# band_psd_v1_1_shield.net
KiCad netlist of a schematic drawn in EAGLE
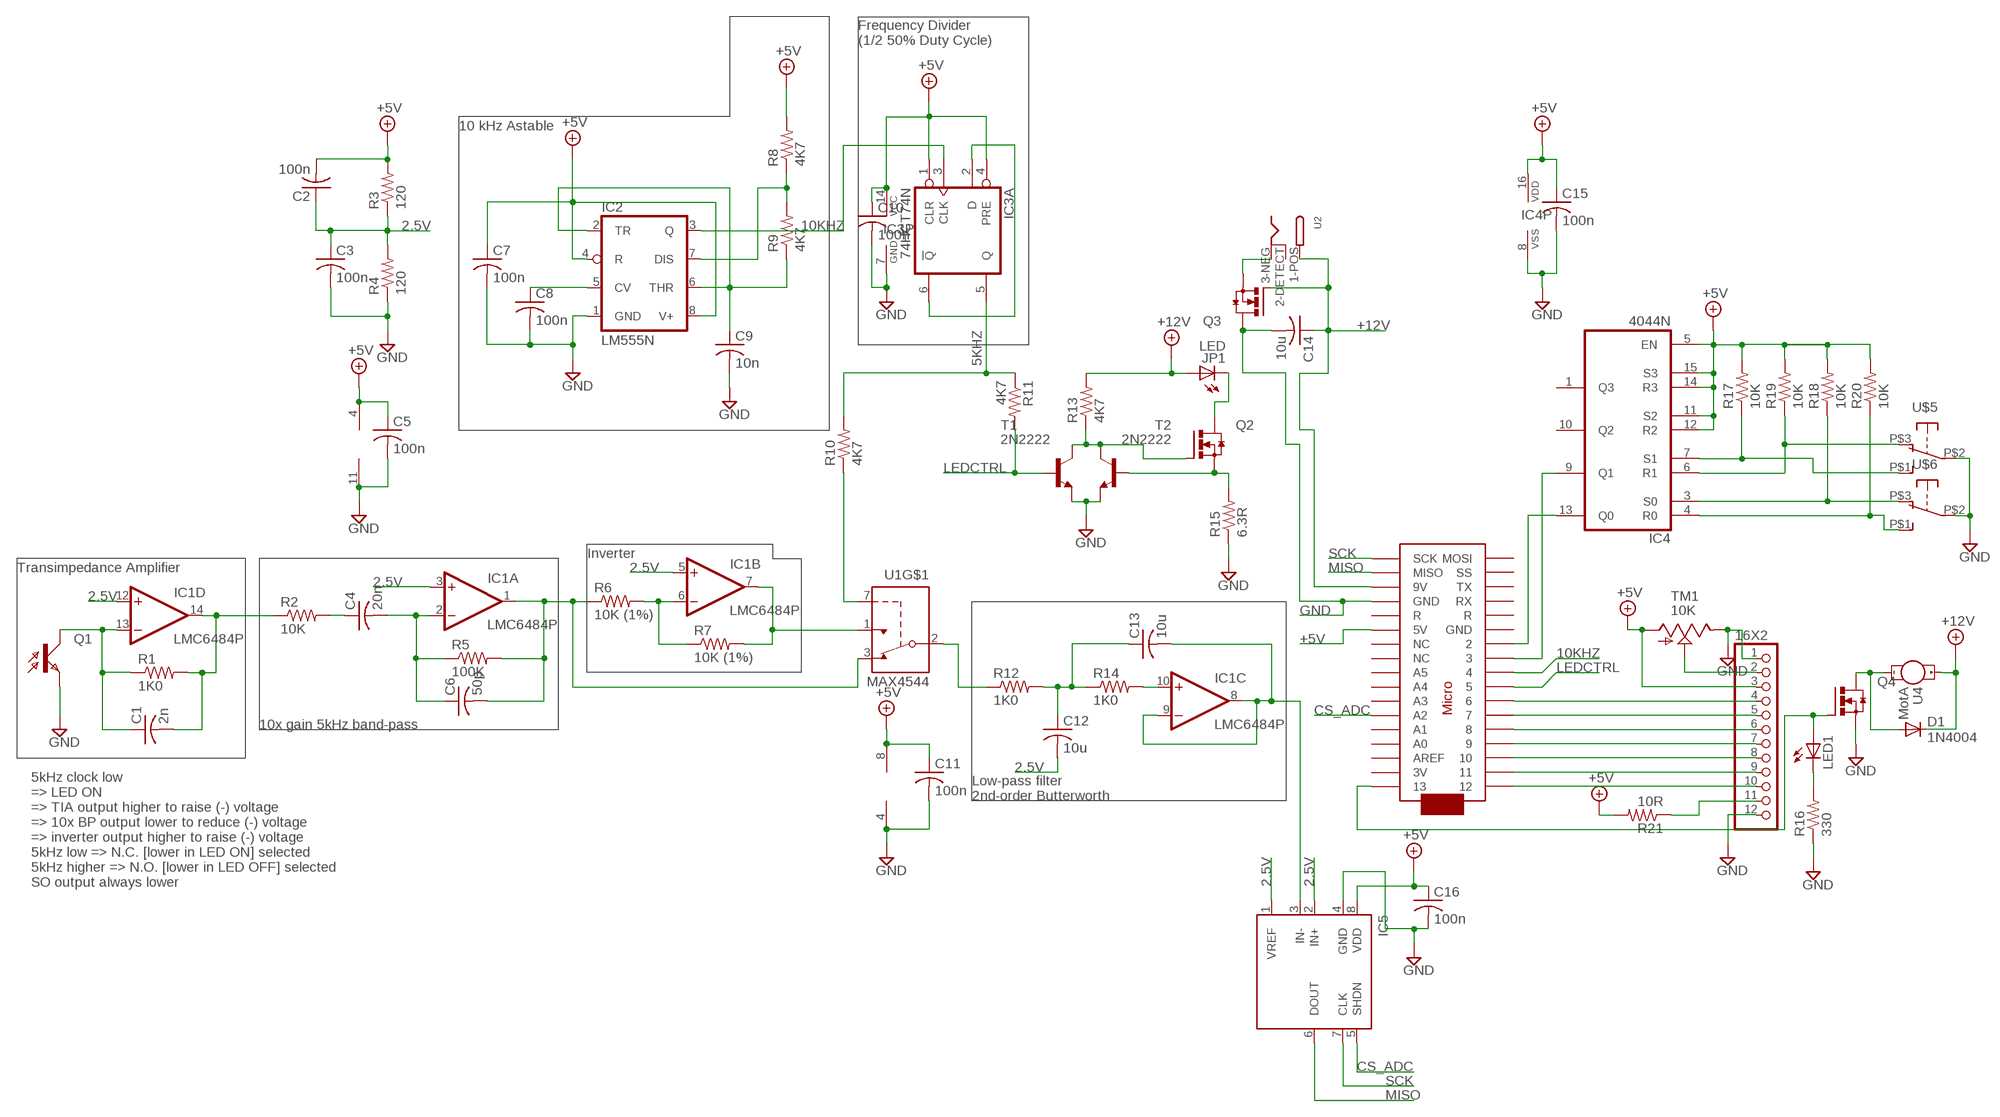
[diagram p0: schematic, sheet 1]

(export (version "E")
  (design (tool "Eeschema 10.0.6"))
  (components
    (comp (ref "16X2")
      (value "PINHD-1X12-CB")
      (footprint "eagle-import:1X12-CB")
      (libsource (lib "eagle-import") (part "PINHD-1X12-CB"))
    )
    (comp (ref "C1")
      (value "2n")
      (footprint "eagle-import:C025-025X050")
      (libsource (lib "eagle-import") (part "C-US025-025X050"))
    )
    (comp (ref "C2")
      (value "100n")
      (footprint "eagle-import:C025-025X050")
      (libsource (lib "eagle-import") (part "C-US025-025X050"))
    )
    (comp (ref "C3")
      (value "100n")
      (footprint "eagle-import:C025-025X050")
      (libsource (lib "eagle-import") (part "C-US025-025X050"))
    )
    (comp (ref "C4")
      (value "20n")
      (footprint "eagle-import:C025-025X050")
      (libsource (lib "eagle-import") (part "C-US025-025X050"))
    )
    (comp (ref "C5")
      (value "100n")
      (footprint "eagle-import:C025-025X050")
      (libsource (lib "eagle-import") (part "C-US025-025X050"))
    )
    (comp (ref "C6")
      (value "50p")
      (footprint "eagle-import:C025-025X050")
      (libsource (lib "eagle-import") (part "C-US025-025X050"))
    )
    (comp (ref "C7")
      (value "100n")
      (footprint "eagle-import:C025-025X050")
      (libsource (lib "eagle-import") (part "C-US025-025X050"))
    )
    (comp (ref "C8")
      (value "100n")
      (footprint "eagle-import:C025-025X050")
      (libsource (lib "eagle-import") (part "C-US025-025X050"))
    )
    (comp (ref "C9")
      (value "10n")
      (footprint "eagle-import:C025-025X050")
      (libsource (lib "eagle-import") (part "C-US025-025X050"))
    )
    (comp (ref "C10")
      (value "100n")
      (footprint "eagle-import:C025-025X050")
      (libsource (lib "eagle-import") (part "C-US025-025X050"))
    )
    (comp (ref "C11")
      (value "100n")
      (footprint "eagle-import:C025-025X050")
      (libsource (lib "eagle-import") (part "C-US025-025X050"))
    )
    (comp (ref "C12")
      (value "10u")
      (footprint "eagle-import:C050-025X075")
      (libsource (lib "eagle-import") (part "C-US050-025X075"))
    )
    (comp (ref "C13")
      (value "10u")
      (footprint "eagle-import:C050-025X075")
      (libsource (lib "eagle-import") (part "C-US050-025X075"))
    )
    (comp (ref "C14")
      (value "10u")
      (footprint "eagle-import:C050-050X075")
      (libsource (lib "eagle-import") (part "C-US050-050X075"))
    )
    (comp (ref "C15")
      (value "100n")
      (footprint "eagle-import:C025-025X050")
      (libsource (lib "eagle-import") (part "C-US025-025X050"))
    )
    (comp (ref "C16")
      (value "100n")
      (footprint "eagle-import:C025-025X050")
      (libsource (lib "eagle-import") (part "C-US025-025X050"))
    )
    (comp (ref "D1")
      (value "1N4004")
      (footprint "eagle-import:DO41-10")
      (libsource (lib "eagle-import") (part "1N4004"))
    )
    (comp (ref "IC1")
      (value "LMC6484P")
      (footprint "eagle-import:DIL14")
      (libsource (lib "eagle-import") (part "LMC6484P"))
    )
    (comp (ref "IC2")
      (value "LM555N")
      (footprint "eagle-import:DIL08")
      (libsource (lib "eagle-import") (part "555NLM"))
    )
    (comp (ref "IC3")
      (value "74HCT74N")
      (footprint "eagle-import:DIL14")
      (libsource (lib "eagle-import") (part "7474NHCT"))
    )
    (comp (ref "IC4")
      (value "4044N")
      (footprint "eagle-import:DIL16")
      (libsource (lib "eagle-import") (part "4044N"))
    )
    (comp (ref "IC5")
      (value "MCP3301")
      (footprint "eagle-import:DIL08")
      (libsource (lib "eagle-import") (part "MCP3301"))
    )
    (comp (ref "JP1")
      (value "LED")
      (footprint "eagle-import:1X02_SCREW")
      (libsource (lib "eagle-import") (part "LED_CXN"))
    )
    (comp (ref "LED1")
      (value "LED3MM")
      (footprint "eagle-import:LED3MM")
      (libsource (lib "eagle-import") (part "LED3MM"))
    )
    (comp (ref "Q1")
      (value "LTR-4206PTRANS")
      (footprint "eagle-import:PTRANS")
      (libsource (lib "eagle-import") (part "LTR-4206PTRANS"))
    )
    (comp (ref "Q2")
      (value "IRLB8721")
      (footprint "eagle-import:TO220BV")
      (libsource (lib "eagle-import") (part "IRLB8721"))
    )
    (comp (ref "Q3")
      (value "IRLB8721")
      (footprint "eagle-import:TO220BV")
      (libsource (lib "eagle-import") (part "IRLB8721"))
    )
    (comp (ref "Q4")
      (value "IRLB8721")
      (footprint "eagle-import:TO220BV")
      (libsource (lib "eagle-import") (part "IRLB8721"))
    )
    (comp (ref "R1")
      (value "1K0")
      (footprint "eagle-import:0204V")
      (libsource (lib "eagle-import") (part "R-US_0204/2V"))
    )
    (comp (ref "R2")
      (value "10K")
      (footprint "eagle-import:0204V")
      (libsource (lib "eagle-import") (part "R-US_0204/2V"))
    )
    (comp (ref "R3")
      (value "120")
      (footprint "eagle-import:0204V")
      (libsource (lib "eagle-import") (part "R-US_0204/2V"))
    )
    (comp (ref "R4")
      (value "120")
      (footprint "eagle-import:0204V")
      (libsource (lib "eagle-import") (part "R-US_0204/2V"))
    )
    (comp (ref "R5")
      (value "100K")
      (footprint "eagle-import:0204V")
      (libsource (lib "eagle-import") (part "R-US_0204/2V"))
    )
    (comp (ref "R6")
      (value "10K (1%)")
      (footprint "eagle-import:0204V")
      (libsource (lib "eagle-import") (part "R-US_0204/2V"))
    )
    (comp (ref "R7")
      (value "10K (1%)")
      (footprint "eagle-import:0204V")
      (libsource (lib "eagle-import") (part "R-US_0204/2V"))
    )
    (comp (ref "R8")
      (value "4K7")
      (footprint "eagle-import:0204V")
      (libsource (lib "eagle-import") (part "R-US_0204/2V"))
    )
    (comp (ref "R9")
      (value "4K7")
      (footprint "eagle-import:0204V")
      (libsource (lib "eagle-import") (part "R-US_0204/2V"))
    )
    (comp (ref "R10")
      (value "4K7")
      (footprint "eagle-import:0204V")
      (libsource (lib "eagle-import") (part "R-US_0204/2V"))
    )
    (comp (ref "R11")
      (value "4K7")
      (footprint "eagle-import:0204V")
      (libsource (lib "eagle-import") (part "R-US_0204/2V"))
    )
    (comp (ref "R12")
      (value "1K0")
      (footprint "eagle-import:0204V")
      (libsource (lib "eagle-import") (part "R-US_0204/2V"))
    )
    (comp (ref "R13")
      (value "4K7")
      (footprint "eagle-import:0204V")
      (libsource (lib "eagle-import") (part "R-US_0204/2V"))
    )
    (comp (ref "R14")
      (value "1K0")
      (footprint "eagle-import:0204V")
      (libsource (lib "eagle-import") (part "R-US_0204/2V"))
    )
    (comp (ref "R15")
      (value "6.3R")
      (footprint "eagle-import:0204V")
      (libsource (lib "eagle-import") (part "R-US_0204/2V"))
    )
    (comp (ref "R16")
      (value "330")
      (footprint "eagle-import:0204V")
      (libsource (lib "eagle-import") (part "R-US_0204/2V"))
    )
    (comp (ref "R17")
      (value "10K")
      (footprint "eagle-import:0204V")
      (libsource (lib "eagle-import") (part "R-US_0204/2V"))
    )
    (comp (ref "R18")
      (value "10K")
      (footprint "eagle-import:0204V")
      (libsource (lib "eagle-import") (part "R-US_0204/2V"))
    )
    (comp (ref "R19")
      (value "10K")
      (footprint "eagle-import:0204V")
      (libsource (lib "eagle-import") (part "R-US_0204/2V"))
    )
    (comp (ref "R20")
      (value "10K")
      (footprint "eagle-import:0204V")
      (libsource (lib "eagle-import") (part "R-US_0204/2V"))
    )
    (comp (ref "R21")
      (value "10R")
      (footprint "eagle-import:0204V")
      (libsource (lib "eagle-import") (part "R-US_0204/2V"))
    )
    (comp (ref "T1")
      (value "2N2222")
      (footprint "eagle-import:TO92-EBC-OVAL")
      (libsource (lib "eagle-import") (part "2N2222"))
    )
    (comp (ref "T2")
      (value "2N2222")
      (footprint "eagle-import:TO92-EBC-OVAL")
      (libsource (lib "eagle-import") (part "2N2222"))
    )
    (comp (ref "TM1")
      (value "10K")
      (footprint "eagle-import:B25P")
      (libsource (lib "eagle-import") (part "TRIM_US-B25P"))
    )
    (comp (ref "U$5")
      (value "APE1F-5M-10-Z")
      (footprint "eagle-import:APE1F-5M-10Z")
      (libsource (lib "eagle-import") (part "APE1F-5M-10-Z"))
    )
    (comp (ref "U$6")
      (value "APE1F-5M-10-Z")
      (footprint "eagle-import:APE1F-5M-10Z")
      (libsource (lib "eagle-import") (part "APE1F-5M-10-Z"))
    )
    (comp (ref "U1")
      (value "MAX4544")
      (footprint "eagle-import:DIL08")
      (libsource (lib "eagle-import") (part "MAX4544"))
    )
    (comp (ref "U2")
      (value "DC-IN-PANEL")
      (footprint "eagle-import:3WIRES")
      (libsource (lib "eagle-import") (part "DC-IN-PANEL"))
    )
    (comp (ref "U3")
      (value "ARDUINOMICRO")
      (footprint "eagle-import:ARDUINOMICRO")
      (libsource (lib "eagle-import") (part "ARDUINOMICRO"))
    )
    (comp (ref "U4")
      (value "MotA")
      (footprint "eagle-import:1X02_SCREW")
      (libsource (lib "eagle-import") (part "1X02_MOTOR"))
    )
  )
  (nets
    (net (code "1") (name "+5V") (class "Default")
      (node (ref "16X2") (pin "3") (pinfunction "3_3") (pintype "passive"))
      (node (ref "C10") (pin "1") (pinfunction "1_1") (pintype "passive"))
      (node (ref "C11") (pin "1") (pinfunction "1_1") (pintype "passive"))
      (node (ref "C15") (pin "1") (pinfunction "1_1") (pintype "passive"))
      (node (ref "C16") (pin "1") (pinfunction "1_1") (pintype "passive"))
      (node (ref "C2") (pin "2") (pinfunction "2_2") (pintype "passive"))
      (node (ref "C5") (pin "1") (pinfunction "1_1") (pintype "passive"))
      (node (ref "C7") (pin "1") (pinfunction "1_1") (pintype "passive"))
      (node (ref "IC1") (pin "4") (pinfunction "V+_4") (pintype "power_in"))
      (node (ref "IC2") (pin "4") (pinfunction "R_4") (pintype "input"))
      (node (ref "IC2") (pin "8") (pinfunction "V+_8") (pintype "power_in"))
      (node (ref "IC3") (pin "1") (pinfunction "CLR_1") (pintype "input"))
      (node (ref "IC3") (pin "14") (pinfunction "VCC_14") (pintype "power_in"))
      (node (ref "IC3") (pin "4") (pinfunction "PRE_4") (pintype "input"))
      (node (ref "IC4") (pin "11") (pinfunction "S2_11") (pintype "input"))
      (node (ref "IC4") (pin "12") (pinfunction "R2_12") (pintype "input"))
      (node (ref "IC4") (pin "14") (pinfunction "R3_14") (pintype "input"))
      (node (ref "IC4") (pin "15") (pinfunction "S3_15") (pintype "input"))
      (node (ref "IC4") (pin "16") (pinfunction "VDD_16") (pintype "power_in"))
      (node (ref "IC4") (pin "5") (pinfunction "EN_5") (pintype "input"))
      (node (ref "IC5") (pin "8") (pinfunction "VDD_8") (pintype "power_in"))
      (node (ref "R17") (pin "2") (pinfunction "2_2") (pintype "passive"))
      (node (ref "R18") (pin "2") (pinfunction "2_2") (pintype "passive"))
      (node (ref "R19") (pin "2") (pinfunction "2_2") (pintype "passive"))
      (node (ref "R20") (pin "2") (pinfunction "2_2") (pintype "passive"))
      (node (ref "R21") (pin "2") (pinfunction "2_2") (pintype "passive"))
      (node (ref "R3") (pin "2") (pinfunction "2_2") (pintype "passive"))
      (node (ref "R8") (pin "2") (pinfunction "2_2") (pintype "passive"))
      (node (ref "TM1") (pin "A") (pinfunction "A_A") (pintype "passive"))
      (node (ref "U1") (pin "8") (pinfunction "V+_8") (pintype "power_in"))
      (node (ref "U3") (pin "P$23") (pinfunction "5V_P$23") (pintype "bidirectional"))
    )
    (net (code "2") (name "+12V") (class "Default")
      (node (ref "C14") (pin "1") (pinfunction "1_1") (pintype "passive"))
      (node (ref "D1") (pin "C") (pinfunction "C_C") (pintype "passive"))
      (node (ref "JP1") (pin "1/POS") (pinfunction "A_1/POS") (pintype "passive"))
      (node (ref "Q3") (pin "G") (pinfunction "G_G") (pintype "passive"))
      (node (ref "R13") (pin "2") (pinfunction "2_2") (pintype "passive"))
      (node (ref "U2") (pin "1-POS") (pinfunction "PWR_1-POS") (pintype "power_in"))
      (node (ref "U3") (pin "P$20") (pinfunction "9V_P$20") (pintype "bidirectional"))
      (node (ref "U4") (pin "1/POS") (pinfunction "+_1/POS") (pintype "bidirectional"))
    )
    (net (code "3") (name "/2.5V") (class "Default")
      (node (ref "C12") (pin "2") (pinfunction "2_2") (pintype "passive"))
      (node (ref "C2") (pin "1") (pinfunction "1_1") (pintype "passive"))
      (node (ref "C3") (pin "1") (pinfunction "1_1") (pintype "passive"))
      (node (ref "IC1") (pin "12") (pinfunction "+IN_12") (pintype "input"))
      (node (ref "IC1") (pin "3") (pinfunction "+IN_3") (pintype "input"))
      (node (ref "IC1") (pin "5") (pinfunction "+IN_5") (pintype "input"))
      (node (ref "IC5") (pin "1") (pinfunction "VREF_1") (pintype "input"))
      (node (ref "IC5") (pin "2") (pinfunction "IN+_2") (pintype "input"))
      (node (ref "R3") (pin "1") (pinfunction "1_1") (pintype "passive"))
      (node (ref "R4") (pin "2") (pinfunction "2_2") (pintype "passive"))
    )
    (net (code "4") (name "/5KHZ") (class "Default")
      (node (ref "IC3") (pin "5") (pinfunction "Q_5") (pintype "output"))
      (node (ref "R10") (pin "2") (pinfunction "2_2") (pintype "passive"))
      (node (ref "R11") (pin "1") (pinfunction "1_1") (pintype "passive"))
    )
    (net (code "5") (name "/10KHZ") (class "Default")
      (node (ref "IC2") (pin "3") (pinfunction "Q_3") (pintype "output"))
      (node (ref "IC3") (pin "3") (pinfunction "CLK_3") (pintype "input"))
      (node (ref "U3") (pin "P$9") (pinfunction "4_P$9") (pintype "bidirectional"))
    )
    (net (code "6") (name "/CS_ADC") (class "Default")
      (node (ref "IC5") (pin "5") (pinfunction "SHDN_5") (pintype "input"))
      (node (ref "U3") (pin "P$29") (pinfunction "A2_P$29") (pintype "bidirectional"))
    )
    (net (code "7") (name "/GNDBREAK") (class "Default")
      (node (ref "U2") (pin "2-DETECT") (pinfunction "GNDBREAK_2-DETECT") (pintype "power_in"))
    )
    (net (code "8") (name "/LEDCTRL") (class "Default")
      (node (ref "R11") (pin "2") (pinfunction "2_2") (pintype "passive"))
      (node (ref "T1") (pin "B") (pinfunction "B_B") (pintype "passive"))
      (node (ref "U3") (pin "P$8") (pinfunction "5_P$8") (pintype "bidirectional"))
    )
    (net (code "9") (name "/MISO") (class "Default")
      (node (ref "IC5") (pin "6") (pinfunction "DOUT_6") (pintype "input"))
      (node (ref "U3") (pin "P$19") (pinfunction "MISO_P$19") (pintype "bidirectional"))
    )
    (net (code "10") (name "/SCK") (class "Default")
      (node (ref "IC5") (pin "7") (pinfunction "CLK_7") (pintype "input"))
      (node (ref "U3") (pin "P$18") (pinfunction "SCK_P$18") (pintype "bidirectional"))
    )
    (net (code "11") (name "GND") (class "Default")
      (node (ref "16X2") (pin "1") (pinfunction "1_1") (pintype "passive"))
      (node (ref "16X2") (pin "12") (pinfunction "12_12") (pintype "passive"))
      (node (ref "C10") (pin "2") (pinfunction "2_2") (pintype "passive"))
      (node (ref "C11") (pin "2") (pinfunction "2_2") (pintype "passive"))
      (node (ref "C14") (pin "2") (pinfunction "2_2") (pintype "passive"))
      (node (ref "C15") (pin "2") (pinfunction "2_2") (pintype "passive"))
      (node (ref "C16") (pin "2") (pinfunction "2_2") (pintype "passive"))
      (node (ref "C3") (pin "2") (pinfunction "2_2") (pintype "passive"))
      (node (ref "C5") (pin "2") (pinfunction "2_2") (pintype "passive"))
      (node (ref "C7") (pin "2") (pinfunction "2_2") (pintype "passive"))
      (node (ref "C8") (pin "2") (pinfunction "2_2") (pintype "passive"))
      (node (ref "C9") (pin "2") (pinfunction "2_2") (pintype "passive"))
      (node (ref "IC1") (pin "11") (pinfunction "V-_11") (pintype "power_in"))
      (node (ref "IC2") (pin "1") (pinfunction "GND_1") (pintype "power_in"))
      (node (ref "IC3") (pin "7") (pinfunction "GND_7") (pintype "power_in"))
      (node (ref "IC4") (pin "8") (pinfunction "VSS_8") (pintype "power_in"))
      (node (ref "IC5") (pin "4") (pinfunction "GND_4") (pintype "power_in"))
      (node (ref "Q1") (pin "A") (pinfunction "E_A") (pintype "passive"))
      (node (ref "Q3") (pin "D") (pinfunction "D_D") (pintype "passive"))
      (node (ref "Q4") (pin "S") (pinfunction "S_S") (pintype "passive"))
      (node (ref "R15") (pin "1") (pinfunction "1_1") (pintype "passive"))
      (node (ref "R16") (pin "1") (pinfunction "1_1") (pintype "passive"))
      (node (ref "R4") (pin "1") (pinfunction "1_1") (pintype "passive"))
      (node (ref "T1") (pin "E") (pinfunction "E_E") (pintype "passive"))
      (node (ref "T2") (pin "E") (pinfunction "E_E") (pintype "passive"))
      (node (ref "TM1") (pin "E") (pinfunction "E_E") (pintype "passive"))
      (node (ref "U$5") (pin "P$2") (pinfunction "COM_P$2") (pintype "passive"))
      (node (ref "U$6") (pin "P$2") (pinfunction "COM_P$2") (pintype "passive"))
      (node (ref "U1") (pin "4") (pinfunction "V-_4") (pintype "power_in"))
      (node (ref "U3") (pin "P$12") (pinfunction "GND_P$12") (pintype "bidirectional"))
    )
    (net (code "12") (name "Net-(16X2-Pad2)") (class "Default")
      (node (ref "16X2") (pin "2") (pinfunction "2_2") (pintype "passive"))
      (node (ref "TM1") (pin "S") (pinfunction "S_S") (pintype "passive"))
    )
    (net (code "13") (name "Net-(16X2-Pad11)") (class "Default")
      (node (ref "16X2") (pin "11") (pinfunction "11_11") (pintype "passive"))
      (node (ref "R21") (pin "1") (pinfunction "1_1") (pintype "passive"))
    )
    (net (code "14") (name "Net-(C4-Pad1)") (class "Default")
      (node (ref "C4") (pin "1") (pinfunction "1_1") (pintype "passive"))
      (node (ref "R2") (pin "2") (pinfunction "2_2") (pintype "passive"))
    )
    (net (code "15") (name "Net-(C12-Pad1)") (class "Default")
      (node (ref "C12") (pin "1") (pinfunction "1_1") (pintype "passive"))
      (node (ref "C13") (pin "1") (pinfunction "1_1") (pintype "passive"))
      (node (ref "R12") (pin "2") (pinfunction "2_2") (pintype "passive"))
      (node (ref "R14") (pin "1") (pinfunction "1_1") (pintype "passive"))
    )
    (net (code "16") (name "Net-(IC1A--IN)") (class "Default")
      (node (ref "C4") (pin "2") (pinfunction "2_2") (pintype "passive"))
      (node (ref "C6") (pin "1") (pinfunction "1_1") (pintype "passive"))
      (node (ref "IC1") (pin "2") (pinfunction "-IN_2") (pintype "input"))
      (node (ref "R5") (pin "1") (pinfunction "1_1") (pintype "passive"))
    )
    (net (code "17") (name "Net-(IC1A-OUT)") (class "Default")
      (node (ref "C6") (pin "2") (pinfunction "2_2") (pintype "passive"))
      (node (ref "IC1") (pin "1") (pinfunction "OUT_1") (pintype "output"))
      (node (ref "R5") (pin "2") (pinfunction "2_2") (pintype "passive"))
      (node (ref "R6") (pin "1") (pinfunction "1_1") (pintype "passive"))
      (node (ref "U1") (pin "3") (pinfunction "NC_3") (pintype "bidirectional"))
    )
    (net (code "18") (name "Net-(IC1B--IN)") (class "Default")
      (node (ref "IC1") (pin "6") (pinfunction "-IN_6") (pintype "input"))
      (node (ref "R6") (pin "2") (pinfunction "2_2") (pintype "passive"))
      (node (ref "R7") (pin "1") (pinfunction "1_1") (pintype "passive"))
    )
    (net (code "19") (name "Net-(IC1B-OUT)") (class "Default")
      (node (ref "IC1") (pin "7") (pinfunction "OUT_7") (pintype "output"))
      (node (ref "R7") (pin "2") (pinfunction "2_2") (pintype "passive"))
      (node (ref "U1") (pin "1") (pinfunction "NO_1") (pintype "bidirectional"))
    )
    (net (code "20") (name "Net-(IC1C-+IN)") (class "Default")
      (node (ref "IC1") (pin "10") (pinfunction "+IN_10") (pintype "input"))
      (node (ref "R14") (pin "2") (pinfunction "2_2") (pintype "passive"))
    )
    (net (code "21") (name "Net-(IC1C--IN)") (class "Default")
      (node (ref "C13") (pin "2") (pinfunction "2_2") (pintype "passive"))
      (node (ref "IC1") (pin "8") (pinfunction "OUT_8") (pintype "output"))
      (node (ref "IC1") (pin "9") (pinfunction "-IN_9") (pintype "input"))
      (node (ref "IC5") (pin "3") (pinfunction "IN-_3") (pintype "input"))
    )
    (net (code "22") (name "Net-(IC1D--IN)") (class "Default")
      (node (ref "C1") (pin "1") (pinfunction "1_1") (pintype "passive"))
      (node (ref "IC1") (pin "13") (pinfunction "-IN_13") (pintype "input"))
      (node (ref "Q1") (pin "K") (pinfunction "C_K") (pintype "passive"))
      (node (ref "R1") (pin "1") (pinfunction "1_1") (pintype "passive"))
    )
    (net (code "23") (name "Net-(IC1D-OUT)") (class "Default")
      (node (ref "C1") (pin "2") (pinfunction "2_2") (pintype "passive"))
      (node (ref "IC1") (pin "14") (pinfunction "OUT_14") (pintype "output"))
      (node (ref "R1") (pin "2") (pinfunction "2_2") (pintype "passive"))
      (node (ref "R2") (pin "1") (pinfunction "1_1") (pintype "passive"))
    )
    (net (code "24") (name "Net-(IC2-CV)") (class "Default")
      (node (ref "C8") (pin "1") (pinfunction "1_1") (pintype "passive"))
      (node (ref "IC2") (pin "5") (pinfunction "CV_5") (pintype "input"))
    )
    (net (code "25") (name "Net-(IC2-DIS)") (class "Default")
      (node (ref "IC2") (pin "7") (pinfunction "DIS_7") (pintype "input"))
      (node (ref "R8") (pin "1") (pinfunction "1_1") (pintype "passive"))
      (node (ref "R9") (pin "2") (pinfunction "2_2") (pintype "passive"))
    )
    (net (code "26") (name "Net-(IC2-THR)") (class "Default")
      (node (ref "C9") (pin "1") (pinfunction "1_1") (pintype "passive"))
      (node (ref "IC2") (pin "2") (pinfunction "TR_2") (pintype "input"))
      (node (ref "IC2") (pin "6") (pinfunction "THR_6") (pintype "input"))
      (node (ref "R9") (pin "1") (pinfunction "1_1") (pintype "passive"))
    )
    (net (code "27") (name "Net-(IC3A-D)") (class "Default")
      (node (ref "IC3") (pin "2") (pinfunction "D_2") (pintype "input"))
      (node (ref "IC3") (pin "6") (pinfunction "~{Q}_6") (pintype "output"))
    )
    (net (code "28") (name "Net-(IC4A-Q0)") (class "Default")
      (node (ref "IC4") (pin "13") (pinfunction "Q0_13") (pintype "output"))
      (node (ref "U3") (pin "P$11") (pinfunction "2_P$11") (pintype "bidirectional"))
    )
    (net (code "29") (name "Net-(IC4A-Q1)") (class "Default")
      (node (ref "IC4") (pin "9") (pinfunction "Q1_9") (pintype "output"))
      (node (ref "U3") (pin "P$10") (pinfunction "3_P$10") (pintype "bidirectional"))
    )
    (net (code "30") (name "Net-(IC4A-R0)") (class "Default")
      (node (ref "IC4") (pin "4") (pinfunction "R0_4") (pintype "input"))
      (node (ref "R20") (pin "1") (pinfunction "1_1") (pintype "passive"))
      (node (ref "U$6") (pin "P$1") (pinfunction "NO_P$1") (pintype "passive"))
    )
    (net (code "31") (name "Net-(IC4A-R1)") (class "Default")
      (node (ref "IC4") (pin "6") (pinfunction "R1_6") (pintype "input"))
      (node (ref "R19") (pin "1") (pinfunction "1_1") (pintype "passive"))
      (node (ref "U$5") (pin "P$3") (pinfunction "NC_P$3") (pintype "passive"))
    )
    (net (code "32") (name "Net-(IC4A-S0)") (class "Default")
      (node (ref "IC4") (pin "3") (pinfunction "S0_3") (pintype "input"))
      (node (ref "R18") (pin "1") (pinfunction "1_1") (pintype "passive"))
      (node (ref "U$6") (pin "P$3") (pinfunction "NC_P$3") (pintype "passive"))
    )
    (net (code "33") (name "Net-(IC4A-S1)") (class "Default")
      (node (ref "IC4") (pin "7") (pinfunction "S1_7") (pintype "input"))
      (node (ref "R17") (pin "1") (pinfunction "1_1") (pintype "passive"))
      (node (ref "U$5") (pin "P$1") (pinfunction "NO_P$1") (pintype "passive"))
    )
    (net (code "34") (name "Net-(JP1-K)") (class "Default")
      (node (ref "JP1") (pin "2") (pinfunction "K_2") (pintype "passive"))
      (node (ref "Q2") (pin "D") (pinfunction "D_D") (pintype "passive"))
    )
    (net (code "35") (name "Net-(LED1-C)") (class "Default")
      (node (ref "LED1") (pin "K") (pinfunction "C_K") (pintype "passive"))
      (node (ref "R16") (pin "2") (pinfunction "2_2") (pintype "passive"))
    )
    (net (code "36") (name "Net-(Q2-PadG)") (class "Default")
      (node (ref "Q2") (pin "G") (pinfunction "G_G") (pintype "passive"))
      (node (ref "R13") (pin "1") (pinfunction "1_1") (pintype "passive"))
      (node (ref "T1") (pin "C") (pinfunction "C_C") (pintype "passive"))
      (node (ref "T2") (pin "C") (pinfunction "C_C") (pintype "passive"))
    )
    (net (code "37") (name "Net-(Q2-PadS)") (class "Default")
      (node (ref "Q2") (pin "S") (pinfunction "S_S") (pintype "passive"))
      (node (ref "R15") (pin "2") (pinfunction "2_2") (pintype "passive"))
      (node (ref "T2") (pin "B") (pinfunction "B_B") (pintype "passive"))
    )
    (net (code "38") (name "Net-(U1A-COM)") (class "Default")
      (node (ref "R12") (pin "1") (pinfunction "1_1") (pintype "passive"))
      (node (ref "U1") (pin "2") (pinfunction "COM_2") (pintype "bidirectional"))
    )
    (net (code "39") (name "Net-(U1A-IN)") (class "Default")
      (node (ref "R10") (pin "1") (pinfunction "1_1") (pintype "passive"))
      (node (ref "U1") (pin "7") (pinfunction "IN_7") (pintype "input"))
    )
    (net (code "40") (name "Net-(U2-GND)") (class "Default")
      (node (ref "Q3") (pin "S") (pinfunction "S_S") (pintype "passive"))
      (node (ref "U2") (pin "3-NEG") (pinfunction "GND_3-NEG") (pintype "power_in"))
    )
    (net (code "41") (name "Net-(U3-6)") (class "Default")
      (node (ref "16X2") (pin "4") (pinfunction "4_4") (pintype "passive"))
      (node (ref "U3") (pin "P$7") (pinfunction "6_P$7") (pintype "bidirectional"))
    )
    (net (code "42") (name "Net-(U3-7)") (class "Default")
      (node (ref "16X2") (pin "5") (pinfunction "5_5") (pintype "passive"))
      (node (ref "U3") (pin "P$6") (pinfunction "7_P$6") (pintype "bidirectional"))
    )
    (net (code "43") (name "Net-(U3-8)") (class "Default")
      (node (ref "16X2") (pin "6") (pinfunction "6_6") (pintype "passive"))
      (node (ref "U3") (pin "P$5") (pinfunction "8_P$5") (pintype "bidirectional"))
    )
    (net (code "44") (name "Net-(U3-9)") (class "Default")
      (node (ref "16X2") (pin "7") (pinfunction "7_7") (pintype "passive"))
      (node (ref "U3") (pin "P$4") (pinfunction "9_P$4") (pintype "bidirectional"))
    )
    (net (code "45") (name "Net-(U3-10)") (class "Default")
      (node (ref "16X2") (pin "8") (pinfunction "8_8") (pintype "passive"))
      (node (ref "U3") (pin "P$3") (pinfunction "10_P$3") (pintype "bidirectional"))
    )
    (net (code "46") (name "Net-(U3-11)") (class "Default")
      (node (ref "16X2") (pin "9") (pinfunction "9_9") (pintype "passive"))
      (node (ref "U3") (pin "P$2") (pinfunction "11_P$2") (pintype "bidirectional"))
    )
    (net (code "47") (name "Net-(U3-12)") (class "Default")
      (node (ref "16X2") (pin "10") (pinfunction "10_10") (pintype "passive"))
      (node (ref "U3") (pin "P$1") (pinfunction "12_P$1") (pintype "bidirectional"))
    )
    (net (code "48") (name "Net-(U3-13)") (class "Default")
      (node (ref "LED1") (pin "A") (pinfunction "A_A") (pintype "passive"))
      (node (ref "Q4") (pin "G") (pinfunction "G_G") (pintype "passive"))
      (node (ref "U3") (pin "P$34") (pinfunction "13_P$34") (pintype "bidirectional"))
    )
    (net (code "49") (name "Net-(U4--)") (class "Default")
      (node (ref "D1") (pin "A") (pinfunction "A_A") (pintype "passive"))
      (node (ref "Q4") (pin "D") (pinfunction "D_D") (pintype "passive"))
      (node (ref "U4") (pin "2") (pinfunction "-_2") (pintype "bidirectional"))
    )
    (net (code "50") (name "unconnected-(IC4A-Q2-Pad10)") (class "Default")
      (node (ref "IC4") (pin "10") (pinfunction "Q2_10") (pintype "output"))
    )
    (net (code "51") (name "unconnected-(IC4A-Q3-Pad1)") (class "Default")
      (node (ref "IC4") (pin "1") (pinfunction "Q3_1") (pintype "output"))
    )
    (net (code "52") (name "unconnected-(U3-3V-PadP$33)") (class "Default")
      (node (ref "U3") (pin "P$33") (pinfunction "3V_P$33") (pintype "bidirectional"))
    )
    (net (code "53") (name "unconnected-(U3-A0-PadP$31)") (class "Default")
      (node (ref "U3") (pin "P$31") (pinfunction "A0_P$31") (pintype "bidirectional"))
    )
    (net (code "54") (name "unconnected-(U3-A1-PadP$30)") (class "Default")
      (node (ref "U3") (pin "P$30") (pinfunction "A1_P$30") (pintype "bidirectional"))
    )
    (net (code "55") (name "unconnected-(U3-A3-PadP$28)") (class "Default")
      (node (ref "U3") (pin "P$28") (pinfunction "A3_P$28") (pintype "bidirectional"))
    )
    (net (code "56") (name "unconnected-(U3-A4-PadP$27)") (class "Default")
      (node (ref "U3") (pin "P$27") (pinfunction "A4_P$27") (pintype "bidirectional"))
    )
    (net (code "57") (name "unconnected-(U3-A5-PadP$26)") (class "Default")
      (node (ref "U3") (pin "P$26") (pinfunction "A5_P$26") (pintype "bidirectional"))
    )
    (net (code "58") (name "unconnected-(U3-AREF-PadP$32)") (class "Default")
      (node (ref "U3") (pin "P$32") (pinfunction "AREF_P$32") (pintype "bidirectional"))
    )
    (net (code "59") (name "unconnected-(U3-GND-PadP$21)") (class "Default")
      (node (ref "U3") (pin "P$21") (pinfunction "GND_P$21") (pintype "bidirectional"))
    )
    (net (code "60") (name "unconnected-(U3-MOSI-PadP$17)") (class "Default")
      (node (ref "U3") (pin "P$17") (pinfunction "MOSI_P$17") (pintype "bidirectional"))
    )
    (net (code "61") (name "unconnected-(U3-NC-PadP$24)") (class "Default")
      (node (ref "U3") (pin "P$24") (pinfunction "NC_P$24") (pintype "bidirectional"))
    )
    (net (code "62") (name "unconnected-(U3-NC-PadP$25)") (class "Default")
      (node (ref "U3") (pin "P$25") (pinfunction "NC_P$25") (pintype "bidirectional"))
    )
    (net (code "63") (name "unconnected-(U3-R-PadP$13)") (class "Default")
      (node (ref "U3") (pin "P$13") (pinfunction "R_P$13") (pintype "bidirectional"))
    )
    (net (code "64") (name "unconnected-(U3-R-PadP$22)") (class "Default")
      (node (ref "U3") (pin "P$22") (pinfunction "R_P$22") (pintype "bidirectional"))
    )
    (net (code "65") (name "unconnected-(U3-RX-PadP$14)") (class "Default")
      (node (ref "U3") (pin "P$14") (pinfunction "RX_P$14") (pintype "bidirectional"))
    )
    (net (code "66") (name "unconnected-(U3-SS-PadP$16)") (class "Default")
      (node (ref "U3") (pin "P$16") (pinfunction "SS_P$16") (pintype "bidirectional"))
    )
    (net (code "67") (name "unconnected-(U3-TX-PadP$15)") (class "Default")
      (node (ref "U3") (pin "P$15") (pinfunction "TX_P$15") (pintype "bidirectional"))
    )
  )
)
